# SAMV71_Xplained_Ultra_Ethernet.net
KiCad netlist of a schematic drawn in Altium Designer
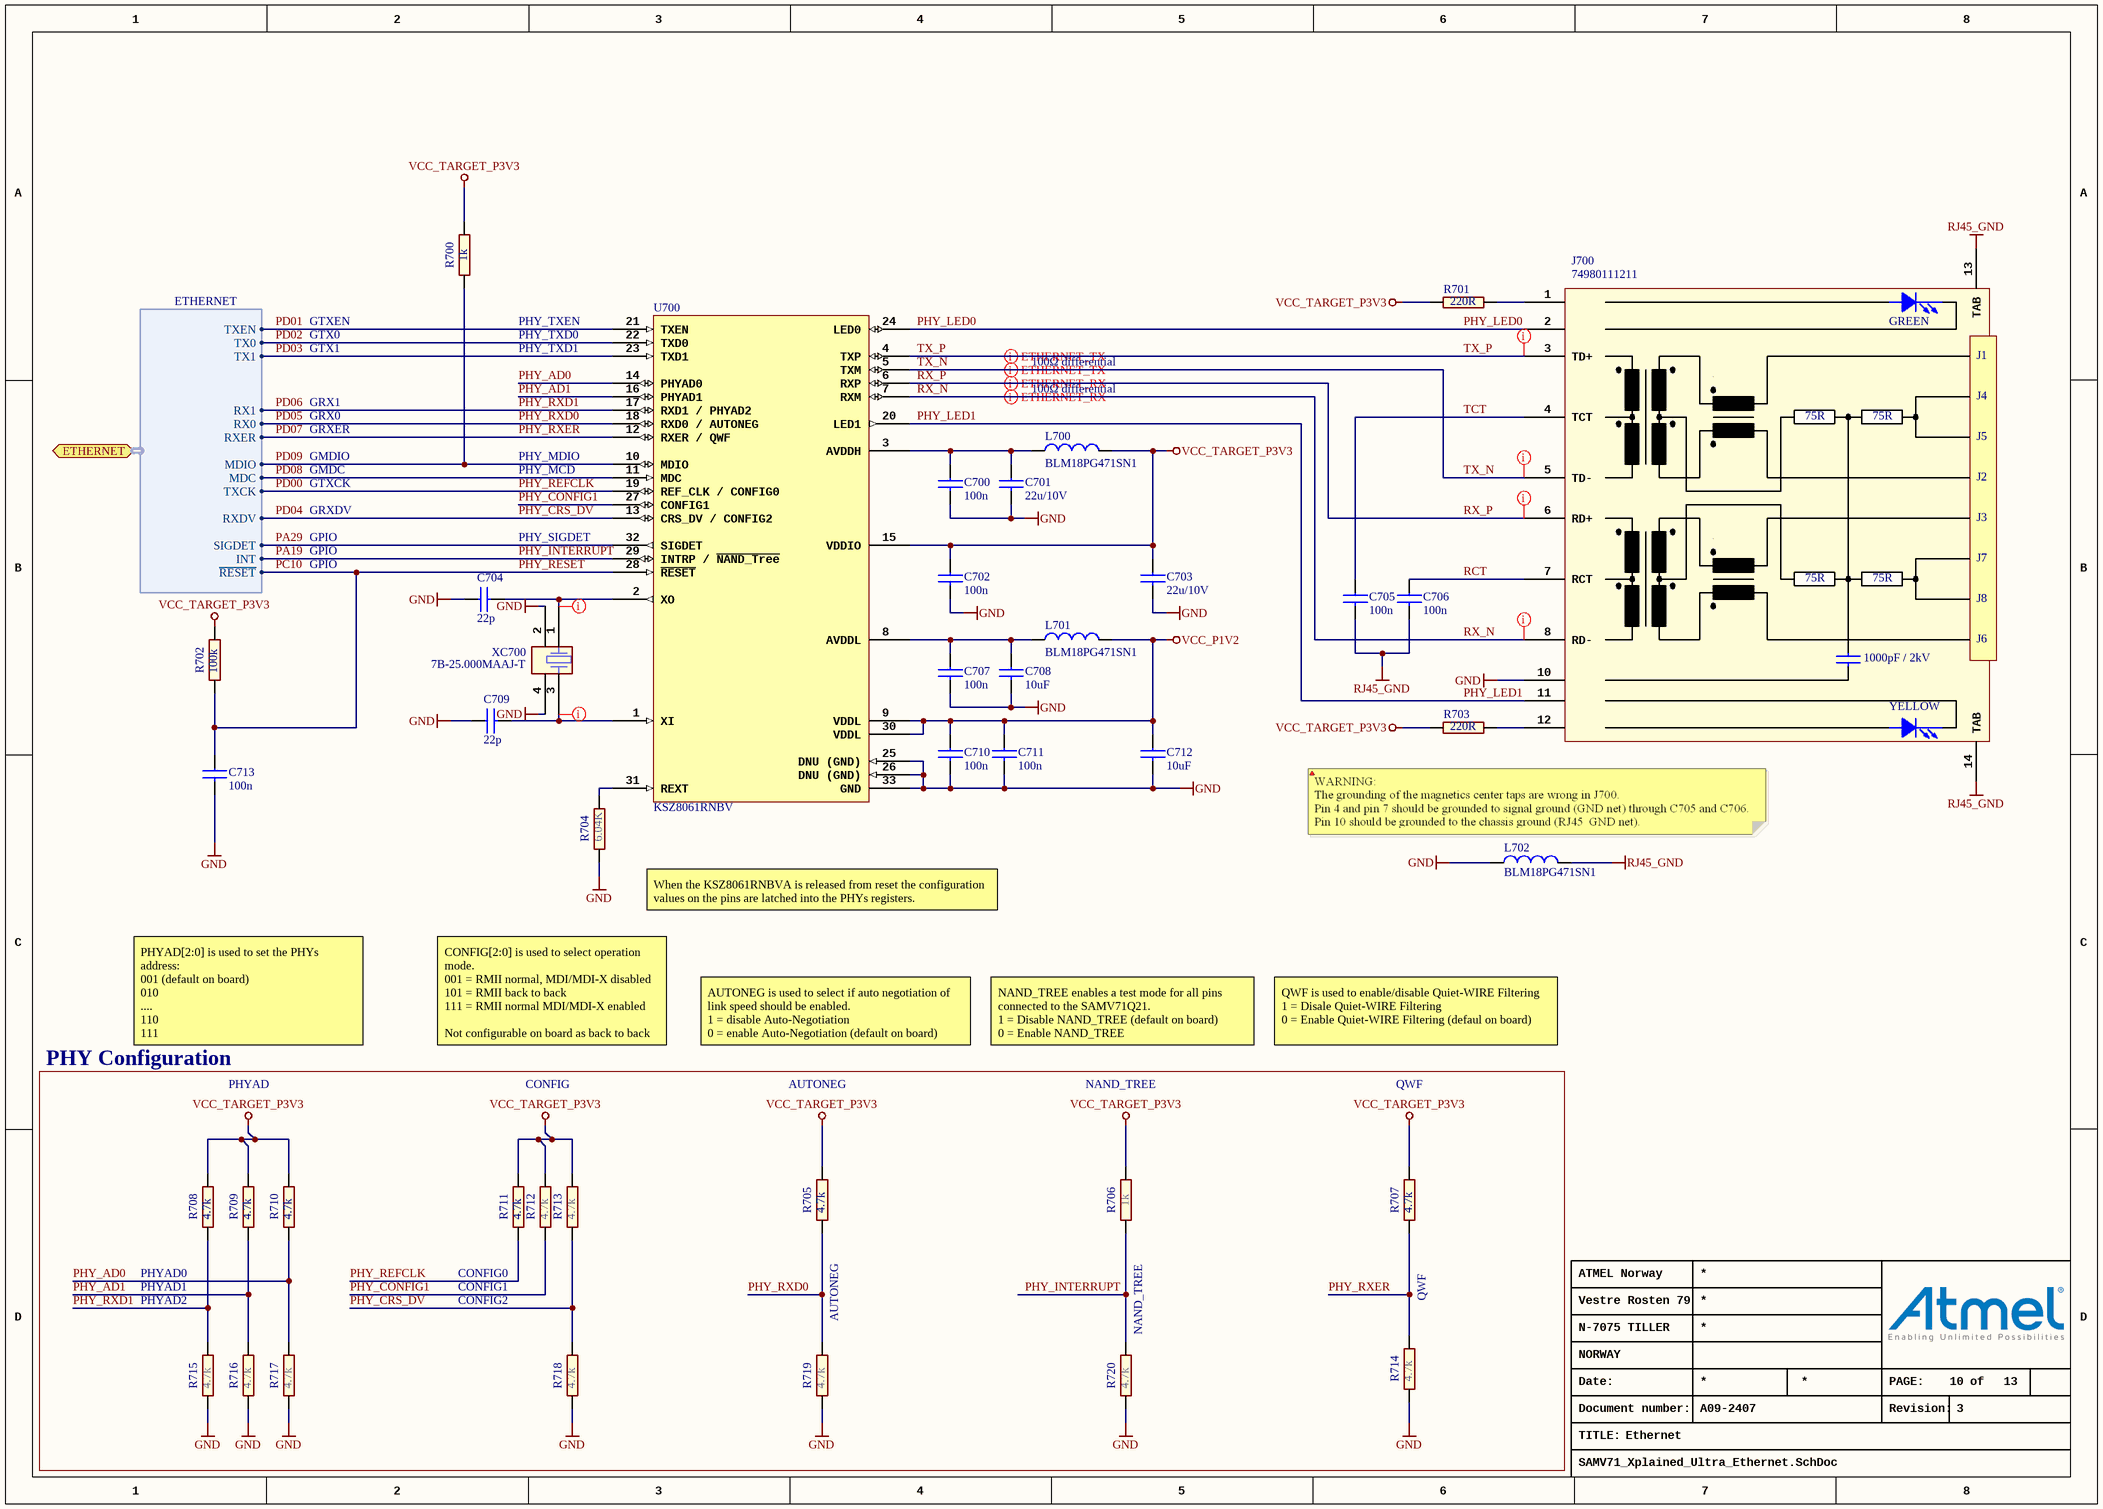
[diagram p0: SAMV71_Xplained_Ultra_Ethernet.SchDoc]

(export (version "E")
  (design (tool "Eeschema 10.0.6"))
  (components
    (comp (ref "C700")
      (value "100n")
      (footprint "AP1-00001")
      (description "Ceramic capacitor, SMD 0402, X7R, 16V, +/-10%")
      (fields (field (name "TOLERANCE") "16V, +/-10%") (field (name "MANUFACTURER") "Kemet"))
      (libsource (lib "AltiumDbLib") (part "CAP-NONPOL"))
    )
    (comp (ref "C701")
      (value "22u/10V")
      (footprint "AP1-00003")
      (description "Ceramic capacitor, SMD 0805, X5R, 10V, ±20%")
      (fields (field (name "MANUFACTURER") "tdk") (field (name "MPN") "C2012X5R1A226M/0.85"))
      (libsource (lib "AltiumDbLib") (part "CAP-NONPOL"))
    )
    (comp (ref "C702")
      (value "100n")
      (footprint "AP1-00001")
      (description "Ceramic capacitor, SMD 0402, X7R, 16V, +/-10%")
      (fields (field (name "TOLERANCE") "16V, +/-10%") (field (name "MANUFACTURER") "Kemet"))
      (libsource (lib "AltiumDbLib") (part "CAP-NONPOL"))
    )
    (comp (ref "C703")
      (value "22u/10V")
      (footprint "AP1-00003")
      (description "Ceramic capacitor, SMD 0805, X5R, 10V, ±20%")
      (fields (field (name "MANUFACTURER") "tdk") (field (name "MPN") "C2012X5R1A226M/0.85"))
      (libsource (lib "AltiumDbLib") (part "CAP-NONPOL"))
    )
    (comp (ref "C704")
      (value "22p")
      (footprint "AP1-00001")
      (description "Ceramic capacitor, SMD 0402, NP0, 50V, +/-5%")
      (fields (field (name "TOLERANCE") "50V, +/-5%"))
      (libsource (lib "AltiumDbLib") (part "CAP-NONPOL"))
    )
    (comp (ref "C705")
      (value "100n")
      (footprint "AP1-00001")
      (description "Ceramic capacitor, SMD 0402, X7R, 16V, +/-10%")
      (fields (field (name "TOLERANCE") "16V, +/-10%") (field (name "MANUFACTURER") "Kemet"))
      (libsource (lib "AltiumDbLib") (part "CAP-NONPOL"))
    )
    (comp (ref "C706")
      (value "100n")
      (footprint "AP1-00001")
      (description "Ceramic capacitor, SMD 0402, X7R, 16V, +/-10%")
      (fields (field (name "TOLERANCE") "16V, +/-10%") (field (name "MANUFACTURER") "Kemet"))
      (libsource (lib "AltiumDbLib") (part "CAP-NONPOL"))
    )
    (comp (ref "C707")
      (value "100n")
      (footprint "AP1-00001")
      (description "Ceramic capacitor, SMD 0402, X7R, 16V, +/-10%")
      (fields (field (name "TOLERANCE") "16V, +/-10%") (field (name "MANUFACTURER") "Kemet"))
      (libsource (lib "AltiumDbLib") (part "CAP-NONPOL"))
    )
    (comp (ref "C708")
      (value "10uF")
      (footprint "AP1-00041")
      (description "Ceramic capacitor, SMD 0805, X7R, 10V, 10 %, (de19441)")
      (fields (field (name "TOLERANCE") "10%") (field (name "MANUFACTURER") "Murata"))
      (libsource (lib "AltiumDbLib") (part "CAP-NONPOL"))
    )
    (comp (ref "C709")
      (value "22p")
      (footprint "AP1-00001")
      (description "Ceramic capacitor, SMD 0402, NP0, 50V, +/-5%")
      (fields (field (name "TOLERANCE") "50V, +/-5%"))
      (libsource (lib "AltiumDbLib") (part "CAP-NONPOL"))
    )
    (comp (ref "C710")
      (value "100n")
      (footprint "AP1-00001")
      (description "Ceramic capacitor, SMD 0402, X7R, 16V, +/-10%")
      (fields (field (name "TOLERANCE") "16V, +/-10%") (field (name "MANUFACTURER") "Kemet"))
      (libsource (lib "AltiumDbLib") (part "CAP-NONPOL"))
    )
    (comp (ref "C711")
      (value "100n")
      (footprint "AP1-00001")
      (description "Ceramic capacitor, SMD 0402, X7R, 16V, +/-10%")
      (fields (field (name "TOLERANCE") "16V, +/-10%") (field (name "MANUFACTURER") "Kemet"))
      (libsource (lib "AltiumDbLib") (part "CAP-NONPOL"))
    )
    (comp (ref "C712")
      (value "10uF")
      (footprint "AP1-00041")
      (description "Ceramic capacitor, SMD 0805, X7R, 10V, 10 %, (de19441)")
      (fields (field (name "TOLERANCE") "10%") (field (name "MANUFACTURER") "Murata"))
      (libsource (lib "AltiumDbLib") (part "CAP-NONPOL"))
    )
    (comp (ref "C713")
      (value "100n")
      (footprint "AP1-00001")
      (description "Ceramic capacitor, SMD 0402, X7R, 16V, +/-10%")
      (fields (field (name "TOLERANCE") "16V, +/-10%") (field (name "MANUFACTURER") "Kemet"))
      (libsource (lib "AltiumDbLib") (part "CAP-NONPOL"))
    )
    (comp (ref "J700")
      (value "74980111211")
      (footprint "AP8-00749")
      (description "10/100Base-TX, SMD, RJ45, green and yellow LEDs, integrated magnetics")
      (fields (field (name "MANUFACTURER") "Wurth Elektronik"))
      (libsource (lib "AltiumDbLib") (part "74980111211"))
    )
    (comp (ref "L700")
      (value "BLM18PG471SN1")
      (footprint "AP3-00005")
      (description "SMD RF inductor 0603. Z=470Ohm (@100MHz), Max R(dc)=0.65Ohm, Max current=1A")
      (fields (field (name "TOLERANCE") "±25%") (field (name "MANUFACTURER") "Murata"))
      (libsource (lib "AltiumDbLib") (part "INDUCTOR"))
    )
    (comp (ref "L701")
      (value "BLM18PG471SN1")
      (footprint "AP3-00005")
      (description "SMD RF inductor 0603. Z=470Ohm (@100MHz), Max R(dc)=0.65Ohm, Max current=1A")
      (fields (field (name "TOLERANCE") "±25%") (field (name "MANUFACTURER") "Murata"))
      (libsource (lib "AltiumDbLib") (part "INDUCTOR"))
    )
    (comp (ref "L702")
      (value "BLM18PG471SN1")
      (footprint "AP3-00005")
      (description "SMD RF inductor 0603. Z=470Ohm (@100MHz), Max R(dc)=0.65Ohm, Max current=1A")
      (fields (field (name "TOLERANCE") "±25%") (field (name "MANUFACTURER") "Murata"))
      (libsource (lib "") (part "INDUCTOR_1"))
    )
    (comp (ref "R700")
      (value "1k")
      (footprint "AP2-00000")
      (description "Thick film resistor, SMD 0402, 1/16W, 1%")
      (fields (field (name "TOLERANCE") "1 %"))
      (libsource (lib "AltiumDbLib") (part "R2"))
    )
    (comp (ref "R701")
      (value "220R")
      (footprint "AP2-00000")
      (description "Thick film resistor, SMD 0402, 1/16W, 1%")
      (fields (field (name "TOLERANCE") "1 %"))
      (libsource (lib "") (part "R2_2"))
    )
    (comp (ref "R702")
      (value "100k")
      (footprint "AP2-00000")
      (description "Thick film resistor, SMD 0402, 1/16W, 1%")
      (fields (field (name "TOLERANCE") "1 %"))
      (libsource (lib "AltiumDbLib") (part "R2"))
    )
    (comp (ref "R703")
      (value "220R")
      (footprint "AP2-00000")
      (description "Thick film resistor, SMD 0402, 1/16W, 1%")
      (fields (field (name "TOLERANCE") "1 %"))
      (libsource (lib "") (part "R2_3"))
    )
    (comp (ref "R704")
      (value "6.04K")
      (footprint "AP2-00000")
      (description "Thick film resistor, SMD 0402, 1/16W, 1%, E192")
      (fields (field (name "TOLERANCE") "1%"))
      (libsource (lib "AltiumDbLib") (part "R2"))
    )
    (comp (ref "R705")
      (value "4.7k")
      (footprint "AP2-00000")
      (description "Thick film resistor, SMD 0402, 1/16W, 1%")
      (fields (field (name "TOLERANCE") "1 %"))
      (libsource (lib "AltiumDbLib") (part "R2"))
    )
    (comp (ref "R706")
      (value "1k")
      (footprint "AP2-00000")
      (description "Thick film resistor, SMD 0402, 1/16W, 1%")
      (fields (field (name "TOLERANCE") "1 %"))
      (libsource (lib "AltiumDbLib") (part "R2"))
    )
    (comp (ref "R707")
      (value "4.7k")
      (footprint "AP2-00000")
      (description "Thick film resistor, SMD 0402, 1/16W, 1%")
      (fields (field (name "TOLERANCE") "1 %"))
      (libsource (lib "AltiumDbLib") (part "R2"))
    )
    (comp (ref "R708")
      (value "4.7k")
      (footprint "AP2-00000")
      (description "Thick film resistor, SMD 0402, 1/16W, 1%")
      (fields (field (name "TOLERANCE") "1 %"))
      (libsource (lib "AltiumDbLib") (part "R2"))
    )
    (comp (ref "R709")
      (value "4.7k")
      (footprint "AP2-00000")
      (description "Thick film resistor, SMD 0402, 1/16W, 1%")
      (fields (field (name "TOLERANCE") "1 %"))
      (libsource (lib "AltiumDbLib") (part "R2"))
    )
    (comp (ref "R710")
      (value "4.7k")
      (footprint "AP2-00000")
      (description "Thick film resistor, SMD 0402, 1/16W, 1%")
      (fields (field (name "TOLERANCE") "1 %"))
      (libsource (lib "AltiumDbLib") (part "R2"))
    )
    (comp (ref "R711")
      (value "4.7k")
      (footprint "AP2-00000")
      (description "Thick film resistor, SMD 0402, 1/16W, 1%")
      (fields (field (name "TOLERANCE") "1 %"))
      (libsource (lib "AltiumDbLib") (part "R2"))
    )
    (comp (ref "R712")
      (value "4.7k")
      (footprint "AP2-00000")
      (description "Thick film resistor, SMD 0402, 1/16W, 1%")
      (fields (field (name "TOLERANCE") "1 %"))
      (libsource (lib "AltiumDbLib") (part "R2"))
    )
    (comp (ref "R713")
      (value "4.7k")
      (footprint "AP2-00000")
      (description "Thick film resistor, SMD 0402, 1/16W, 1%")
      (fields (field (name "TOLERANCE") "1 %"))
      (libsource (lib "AltiumDbLib") (part "R2"))
    )
    (comp (ref "R714")
      (value "4.7k")
      (footprint "AP2-00000")
      (description "Thick film resistor, SMD 0402, 1/16W, 1%")
      (fields (field (name "TOLERANCE") "1 %"))
      (libsource (lib "") (part "R2_1"))
    )
    (comp (ref "R715")
      (value "4.7k")
      (footprint "AP2-00000")
      (description "Thick film resistor, SMD 0402, 1/16W, 1%")
      (fields (field (name "TOLERANCE") "1 %"))
      (libsource (lib "") (part "R2_1"))
    )
    (comp (ref "R716")
      (value "4.7k")
      (footprint "AP2-00000")
      (description "Thick film resistor, SMD 0402, 1/16W, 1%")
      (fields (field (name "TOLERANCE") "1 %"))
      (libsource (lib "") (part "R2_1"))
    )
    (comp (ref "R717")
      (value "4.7k")
      (footprint "AP2-00000")
      (description "Thick film resistor, SMD 0402, 1/16W, 1%")
      (fields (field (name "TOLERANCE") "1 %"))
      (libsource (lib "") (part "R2_1"))
    )
    (comp (ref "R718")
      (value "4.7k")
      (footprint "AP2-00000")
      (description "Thick film resistor, SMD 0402, 1/16W, 1%")
      (fields (field (name "TOLERANCE") "1 %"))
      (libsource (lib "AltiumDbLib") (part "R2"))
    )
    (comp (ref "R719")
      (value "4.7k")
      (footprint "AP2-00000")
      (description "Thick film resistor, SMD 0402, 1/16W, 1%")
      (fields (field (name "TOLERANCE") "1 %"))
      (libsource (lib "") (part "R2_1"))
    )
    (comp (ref "R720")
      (value "4.7k")
      (footprint "AP2-00000")
      (description "Thick film resistor, SMD 0402, 1/16W, 1%")
      (fields (field (name "TOLERANCE") "1 %"))
      (libsource (lib "") (part "R2_1"))
    )
    (comp (ref "U700")
      (value "KSZ8061RNBV")
      (footprint "AP6-00349")
      (description "10Base-T/100Base-TX PHY, RMII, EEE, 50MHz clock output, AEC-Q100 Automotive")
      (fields (field (name "MANUFACTURER") "MICREL SEMICONDUCTOR"))
      (libsource (lib "AltiumDbLib") (part "KSZ8061RNB"))
    )
    (comp (ref "XC700")
      (value "7B-25.000MAAJ-T")
      (footprint "AP7-00067")
      (description "25.000 MHz crystal, 18pF, ±30ppm, 5.0 x 3.2 mm")
      (fields (field (name "TOLERANCE") "Â±30ppm") (field (name "MANUFACTURER") "TXC Corporation"))
      (libsource (lib "AltiumDbLib") (part "CRYSTAL1324"))
    )
  )
  (nets
    (net (code "2") (name "/PA19") (class "Default")
      (node (ref "R706") (pin "1") (pinfunction "1_1") (pintype "passive"))
      (node (ref "R720") (pin "1") (pinfunction "1_1") (pintype "passive"))
      (node (ref "U700") (pin "29") (pinfunction "INTRP_/_~{NAND_Tree}_29") (pintype "bidirectional"))
    )
    (net (code "3") (name "/PA29") (class "Default")
      (node (ref "U700") (pin "32") (pinfunction "SIGDET_32") (pintype "output"))
    )
    (net (code "4") (name "/PC10") (class "Default")
      (node (ref "C713") (pin "1") (pinfunction "1_1") (pintype "passive"))
      (node (ref "R702") (pin "1") (pinfunction "1_1") (pintype "passive"))
      (node (ref "U700") (pin "28") (pinfunction "~{RESET}_28") (pintype "input"))
    )
    (net (code "5") (name "/PD00") (class "Default")
      (node (ref "R711") (pin "1") (pinfunction "1_1") (pintype "passive"))
      (node (ref "U700") (pin "19") (pinfunction "REF_CLK_/_CONFIG0_19") (pintype "bidirectional"))
    )
    (net (code "6") (name "/PD01") (class "Default")
      (node (ref "U700") (pin "21") (pinfunction "TXEN_21") (pintype "input"))
    )
    (net (code "7") (name "/PD02") (class "Default")
      (node (ref "U700") (pin "22") (pinfunction "TXD0_22") (pintype "input"))
    )
    (net (code "8") (name "/PD03") (class "Default")
      (node (ref "U700") (pin "23") (pinfunction "TXD1_23") (pintype "input"))
    )
    (net (code "9") (name "/PD04") (class "Default")
      (node (ref "R713") (pin "1") (pinfunction "1_1") (pintype "passive"))
      (node (ref "R718") (pin "2") (pinfunction "2_2") (pintype "passive"))
      (node (ref "U700") (pin "13") (pinfunction "CRS_DV_/_CONFIG2_13") (pintype "bidirectional"))
    )
    (net (code "10") (name "/PD05") (class "Default")
      (node (ref "R705") (pin "1") (pinfunction "1_1") (pintype "passive"))
      (node (ref "R719") (pin "1") (pinfunction "1_1") (pintype "passive"))
      (node (ref "U700") (pin "18") (pinfunction "RXD0_/_AUTONEG_18") (pintype "bidirectional"))
    )
    (net (code "11") (name "/PD06") (class "Default")
      (node (ref "R708") (pin "1") (pinfunction "1_1") (pintype "passive"))
      (node (ref "R715") (pin "1") (pinfunction "1_1") (pintype "passive"))
      (node (ref "U700") (pin "17") (pinfunction "RXD1_/_PHYAD2_17") (pintype "bidirectional"))
    )
    (net (code "12") (name "/PD07") (class "Default")
      (node (ref "R707") (pin "1") (pinfunction "1_1") (pintype "passive"))
      (node (ref "R714") (pin "1") (pinfunction "1_1") (pintype "passive"))
      (node (ref "U700") (pin "12") (pinfunction "RXER_/_QWF_12") (pintype "bidirectional"))
    )
    (net (code "13") (name "/PD08") (class "Default")
      (node (ref "U700") (pin "11") (pinfunction "MDC_11") (pintype "input"))
    )
    (net (code "14") (name "/PD09") (class "Default")
      (node (ref "R700") (pin "1") (pinfunction "1_1") (pintype "passive"))
      (node (ref "U700") (pin "10") (pinfunction "MDIO_10") (pintype "bidirectional"))
    )
    (net (code "15") (name "/PHY_AD0") (class "Default")
      (node (ref "R710") (pin "1") (pinfunction "1_1") (pintype "passive"))
      (node (ref "R717") (pin "1") (pinfunction "1_1") (pintype "passive"))
      (node (ref "U700") (pin "14") (pinfunction "PHYAD0_14") (pintype "bidirectional"))
    )
    (net (code "16") (name "/PHY_AD1") (class "Default")
      (node (ref "R709") (pin "1") (pinfunction "1_1") (pintype "passive"))
      (node (ref "R716") (pin "1") (pinfunction "1_1") (pintype "passive"))
      (node (ref "U700") (pin "16") (pinfunction "PHYAD1_16") (pintype "bidirectional"))
    )
    (net (code "17") (name "/PHY_CONFIG1") (class "Default")
      (node (ref "R712") (pin "1") (pinfunction "1_1") (pintype "passive"))
      (node (ref "U700") (pin "27") (pinfunction "CONFIG1_27") (pintype "bidirectional"))
    )
    (net (code "18") (name "/PHY_LED0") (class "Default")
      (node (ref "J700") (pin "2") (pintype "passive"))
      (node (ref "U700") (pin "24") (pinfunction "LED0_24") (pintype "bidirectional"))
    )
    (net (code "19") (name "/PHY_LED1") (class "Default")
      (node (ref "J700") (pin "11") (pintype "passive"))
      (node (ref "U700") (pin "20") (pinfunction "LED1_20") (pintype "output"))
    )
    (net (code "20") (name "/RCT") (class "Default")
      (node (ref "C706") (pin "1") (pinfunction "1_1") (pintype "passive"))
      (node (ref "J700") (pin "7") (pinfunction "RCT_7") (pintype "passive"))
    )
    (net (code "21") (name "/RX_N") (class "Default")
      (node (ref "J700") (pin "8") (pinfunction "RD-_8") (pintype "passive"))
      (node (ref "U700") (pin "7") (pinfunction "RXM_7") (pintype "bidirectional"))
    )
    (net (code "22") (name "/RX_P") (class "Default")
      (node (ref "J700") (pin "6") (pinfunction "RD+_6") (pintype "passive"))
      (node (ref "U700") (pin "6") (pinfunction "RXP_6") (pintype "bidirectional"))
    )
    (net (code "23") (name "/TCT") (class "Default")
      (node (ref "C705") (pin "1") (pinfunction "1_1") (pintype "passive"))
      (node (ref "J700") (pin "4") (pinfunction "TCT_4") (pintype "passive"))
    )
    (net (code "24") (name "/TX_N") (class "Default")
      (node (ref "J700") (pin "5") (pinfunction "TD-_5") (pintype "passive"))
      (node (ref "U700") (pin "5") (pinfunction "TXM_5") (pintype "bidirectional"))
    )
    (net (code "25") (name "/TX_P") (class "Default")
      (node (ref "J700") (pin "3") (pinfunction "TD+_3") (pintype "passive"))
      (node (ref "U700") (pin "4") (pinfunction "TXP_4") (pintype "bidirectional"))
    )
    (net (code "27") (name "GND") (class "Default")
      (node (ref "C700") (pin "2") (pinfunction "2_2") (pintype "passive"))
      (node (ref "C701") (pin "2") (pinfunction "2_2") (pintype "passive"))
      (node (ref "C702") (pin "2") (pinfunction "2_2") (pintype "passive"))
      (node (ref "C703") (pin "2") (pinfunction "2_2") (pintype "passive"))
      (node (ref "C704") (pin "1") (pinfunction "1_1") (pintype "passive"))
      (node (ref "C707") (pin "2") (pinfunction "2_2") (pintype "passive"))
      (node (ref "C708") (pin "2") (pinfunction "2_2") (pintype "passive"))
      (node (ref "C709") (pin "1") (pinfunction "1_1") (pintype "passive"))
      (node (ref "C710") (pin "2") (pinfunction "2_2") (pintype "passive"))
      (node (ref "C711") (pin "2") (pinfunction "2_2") (pintype "passive"))
      (node (ref "C712") (pin "2") (pinfunction "2_2") (pintype "passive"))
      (node (ref "C713") (pin "2") (pinfunction "2_2") (pintype "passive"))
      (node (ref "J700") (pin "10") (pintype "passive"))
      (node (ref "L702") (pin "1") (pinfunction "1_1") (pintype "passive"))
      (node (ref "R704") (pin "1") (pinfunction "1_1") (pintype "passive"))
      (node (ref "R714") (pin "2") (pinfunction "2_2") (pintype "passive"))
      (node (ref "R715") (pin "2") (pinfunction "2_2") (pintype "passive"))
      (node (ref "R716") (pin "2") (pinfunction "2_2") (pintype "passive"))
      (node (ref "R717") (pin "2") (pinfunction "2_2") (pintype "passive"))
      (node (ref "R718") (pin "1") (pinfunction "1_1") (pintype "passive"))
      (node (ref "R719") (pin "2") (pinfunction "2_2") (pintype "passive"))
      (node (ref "R720") (pin "2") (pinfunction "2_2") (pintype "passive"))
      (node (ref "U700") (pin "25") (pinfunction "DNU_(GND)_25") (pintype "input"))
      (node (ref "U700") (pin "26") (pinfunction "DNU_(GND)_26") (pintype "input"))
      (node (ref "U700") (pin "33") (pinfunction "GND_33") (pintype "power_in"))
      (node (ref "XC700") (pin "2") (pinfunction "2_2") (pintype "passive"))
      (node (ref "XC700") (pin "4") (pinfunction "4_4") (pintype "passive"))
    )
    (net (code "28") (name "Net-(J700-Pad1)") (class "Default")
      (node (ref "J700") (pin "1") (pintype "passive"))
      (node (ref "R701") (pin "1") (pinfunction "1_1") (pintype "passive"))
    )
    (net (code "29") (name "Net-(J700-Pad12)") (class "Default")
      (node (ref "J700") (pin "12") (pintype "passive"))
      (node (ref "R703") (pin "2") (pinfunction "2_2") (pintype "passive"))
    )
    (net (code "30") (name "Net-(U700-AVDDH)") (class "Default")
      (node (ref "C700") (pin "1") (pinfunction "1_1") (pintype "passive"))
      (node (ref "C701") (pin "1") (pinfunction "1_1") (pintype "passive"))
      (node (ref "L700") (pin "2") (pinfunction "2_2") (pintype "passive"))
      (node (ref "U700") (pin "3") (pinfunction "AVDDH_3") (pintype "power_in"))
    )
    (net (code "31") (name "Net-(U700-AVDDL)") (class "Default")
      (node (ref "C707") (pin "1") (pinfunction "1_1") (pintype "passive"))
      (node (ref "C708") (pin "1") (pinfunction "1_1") (pintype "passive"))
      (node (ref "L701") (pin "2") (pinfunction "2_2") (pintype "passive"))
      (node (ref "U700") (pin "8") (pinfunction "AVDDL_8") (pintype "power_in"))
    )
    (net (code "32") (name "Net-(U700-REXT)") (class "Default")
      (node (ref "R704") (pin "2") (pinfunction "2_2") (pintype "passive"))
      (node (ref "U700") (pin "31") (pinfunction "REXT_31") (pintype "input"))
    )
    (net (code "33") (name "Net-(U700-XI)") (class "Default")
      (node (ref "C709") (pin "2") (pinfunction "2_2") (pintype "passive"))
      (node (ref "U700") (pin "1") (pinfunction "XI_1") (pintype "input"))
      (node (ref "XC700") (pin "3") (pinfunction "3_3") (pintype "passive"))
    )
    (net (code "34") (name "Net-(U700-XO)") (class "Default")
      (node (ref "C704") (pin "2") (pinfunction "2_2") (pintype "passive"))
      (node (ref "U700") (pin "2") (pinfunction "XO_2") (pintype "output"))
      (node (ref "XC700") (pin "1") (pinfunction "1_1") (pintype "passive"))
    )
    (net (code "35") (name "RJ45_GND") (class "Default")
      (node (ref "C705") (pin "2") (pinfunction "2_2") (pintype "passive"))
      (node (ref "C706") (pin "2") (pinfunction "2_2") (pintype "passive"))
      (node (ref "J700") (pin "13") (pinfunction "TAB_13") (pintype "power_in"))
      (node (ref "J700") (pin "14") (pinfunction "TAB_14") (pintype "power_in"))
      (node (ref "L702") (pin "2") (pinfunction "2_2") (pintype "passive"))
    )
    (net (code "36") (name "VCC_P1V2") (class "Default")
      (node (ref "C710") (pin "1") (pinfunction "1_1") (pintype "passive"))
      (node (ref "C711") (pin "1") (pinfunction "1_1") (pintype "passive"))
      (node (ref "C712") (pin "1") (pinfunction "1_1") (pintype "passive"))
      (node (ref "L701") (pin "1") (pinfunction "1_1") (pintype "passive"))
      (node (ref "U700") (pin "30") (pinfunction "VDDL_30") (pintype "power_in"))
      (node (ref "U700") (pin "9") (pinfunction "VDDL_9") (pintype "power_in"))
    )
    (net (code "37") (name "VCC_TARGET_P3V3") (class "Default")
      (node (ref "C702") (pin "1") (pinfunction "1_1") (pintype "passive"))
      (node (ref "C703") (pin "1") (pinfunction "1_1") (pintype "passive"))
      (node (ref "L700") (pin "1") (pinfunction "1_1") (pintype "passive"))
      (node (ref "R700") (pin "2") (pinfunction "2_2") (pintype "passive"))
      (node (ref "R701") (pin "2") (pinfunction "2_2") (pintype "passive"))
      (node (ref "R702") (pin "2") (pinfunction "2_2") (pintype "passive"))
      (node (ref "R703") (pin "1") (pinfunction "1_1") (pintype "passive"))
      (node (ref "R705") (pin "2") (pinfunction "2_2") (pintype "passive"))
      (node (ref "R706") (pin "2") (pinfunction "2_2") (pintype "passive"))
      (node (ref "R707") (pin "2") (pinfunction "2_2") (pintype "passive"))
      (node (ref "R708") (pin "2") (pinfunction "2_2") (pintype "passive"))
      (node (ref "R709") (pin "2") (pinfunction "2_2") (pintype "passive"))
      (node (ref "R710") (pin "2") (pinfunction "2_2") (pintype "passive"))
      (node (ref "R711") (pin "2") (pinfunction "2_2") (pintype "passive"))
      (node (ref "R712") (pin "2") (pinfunction "2_2") (pintype "passive"))
      (node (ref "R713") (pin "2") (pinfunction "2_2") (pintype "passive"))
      (node (ref "U700") (pin "15") (pinfunction "VDDIO_15") (pintype "power_in"))
    )
  )
)
